# IMU.net
KiCad netlist of a schematic drawn in Altium Designer
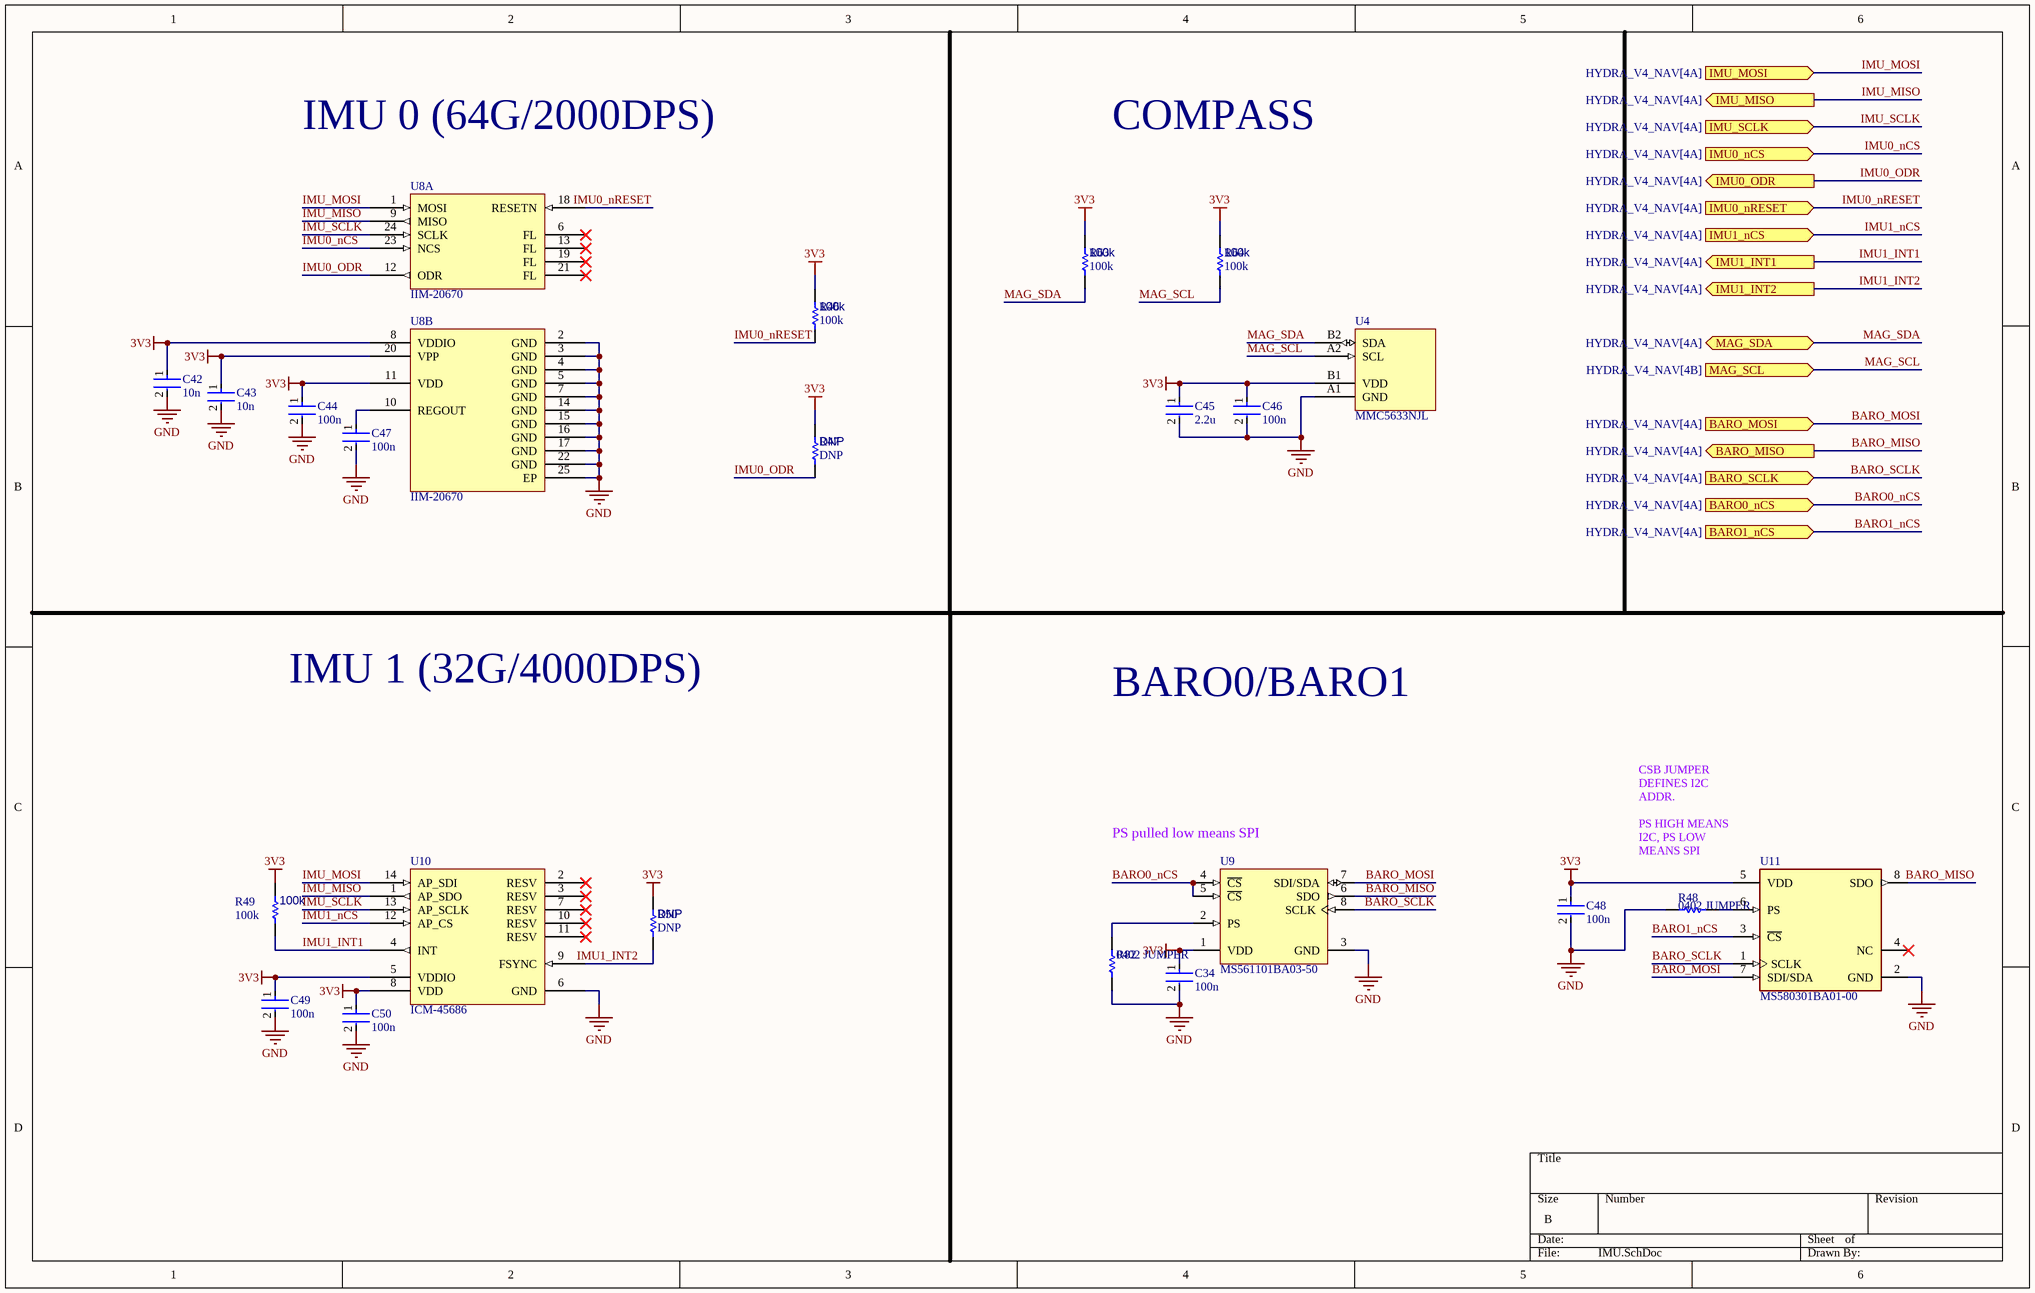
[diagram p0: IMU.SchDoc]

(export (version "E")
  (design (tool "Eeschema 10.0.6"))
  (components
    (comp (ref "C34")
      (value "100n")
      (footprint "FP-0402-L_1_0_0_05-W_0_5-IPC_A")
      (description "LARGE PADS, 0402 CAP, CHANGE COMMENT TO MATCH REAL P/N")
      (libsource (lib "Space Concordia") (part "b4654b650e69147ec39a6b967a45e02"))
    )
    (comp (ref "C42")
      (value "10n")
      (footprint "FP-0402-L_1_0_0_05-W_0_5-IPC_A")
      (description "LARGE PADS, 0402 CAP, CHANGE COMMENT TO MATCH REAL P/N")
      (libsource (lib "Space Concordia") (part "b4654b650e69147ec39a6b967a45e02"))
    )
    (comp (ref "C43")
      (value "10n")
      (footprint "FP-0402-L_1_0_0_05-W_0_5-IPC_A")
      (description "LARGE PADS, 0402 CAP, CHANGE COMMENT TO MATCH REAL P/N")
      (libsource (lib "Space Concordia") (part "b4654b650e69147ec39a6b967a45e02"))
    )
    (comp (ref "C44")
      (value "100n")
      (footprint "FP-0402-L_1_0_0_05-W_0_5-IPC_A")
      (description "LARGE PADS, 0402 CAP, CHANGE COMMENT TO MATCH REAL P/N")
      (libsource (lib "Space Concordia") (part "b4654b650e69147ec39a6b967a45e02"))
    )
    (comp (ref "C45")
      (value "2.2u")
      (footprint "FP-0402-L_1_0_0_05-W_0_5-IPC_A")
      (description "LARGE PADS, 0402 CAP, CHANGE COMMENT TO MATCH REAL P/N")
      (libsource (lib "Space Concordia") (part "b4654b650e69147ec39a6b967a45e02"))
    )
    (comp (ref "C46")
      (value "100n")
      (footprint "FP-0402-L_1_0_0_05-W_0_5-IPC_A")
      (description "LARGE PADS, 0402 CAP, CHANGE COMMENT TO MATCH REAL P/N")
      (libsource (lib "Space Concordia") (part "b4654b650e69147ec39a6b967a45e02"))
    )
    (comp (ref "C47")
      (value "100n")
      (footprint "FP-0402-L_1_0_0_05-W_0_5-IPC_A")
      (description "LARGE PADS, 0402 CAP, CHANGE COMMENT TO MATCH REAL P/N")
      (libsource (lib "Space Concordia") (part "b4654b650e69147ec39a6b967a45e02"))
    )
    (comp (ref "C48")
      (value "100n")
      (footprint "FP-0402-L_1_0_0_05-W_0_5-IPC_A")
      (description "LARGE PADS, 0402 CAP, CHANGE COMMENT TO MATCH REAL P/N")
      (libsource (lib "Space Concordia") (part "b4654b650e69147ec39a6b967a45e02"))
    )
    (comp (ref "C49")
      (value "100n")
      (footprint "FP-0402-L_1_0_0_05-W_0_5-IPC_A")
      (description "LARGE PADS, 0402 CAP, CHANGE COMMENT TO MATCH REAL P/N")
      (libsource (lib "Space Concordia") (part "b4654b650e69147ec39a6b967a45e02"))
    )
    (comp (ref "C50")
      (value "100n")
      (footprint "FP-0402-L_1_0_0_05-W_0_5-IPC_A")
      (description "LARGE PADS, 0402 CAP, CHANGE COMMENT TO MATCH REAL P/N")
      (libsource (lib "Space Concordia") (part "b4654b650e69147ec39a6b967a45e02"))
    )
    (comp (ref "R46")
      (value "100k")
      (footprint "R0603B")
      (description "Resistor")
      (fields (field (name "ALTIUM_VALUE") "100k"))
      (libsource (lib "Space Concordia") (part "Resistor"))
    )
    (comp (ref "R47")
      (value "DNP")
      (footprint "R0603B")
      (description "Resistor")
      (fields (field (name "ALTIUM_VALUE") "DNP"))
      (libsource (lib "Space Concordia") (part "Resistor"))
    )
    (comp (ref "R48")
      (value "0402 JUMPER")
      (footprint "RESC1005X40X25ML05T05")
      (description "READ THE NAME")
      (libsource (lib "Space Concordia") (part "CMP-009-00206-2"))
    )
    (comp (ref "R49")
      (value "100k")
      (footprint "R0603B")
      (description "Resistor")
      (fields (field (name "ALTIUM_VALUE") "100k"))
      (libsource (lib "Space Concordia") (part "Resistor"))
    )
    (comp (ref "R50")
      (value "DNP")
      (footprint "R0603B")
      (description "Resistor")
      (fields (field (name "ALTIUM_VALUE") "DNP"))
      (libsource (lib "Space Concordia") (part "Resistor"))
    )
    (comp (ref "R63")
      (value "100k")
      (footprint "R0603B")
      (description "Resistor")
      (fields (field (name "ALTIUM_VALUE") "100k"))
      (libsource (lib "Space Concordia") (part "Resistor"))
    )
    (comp (ref "R64")
      (value "100k")
      (footprint "R0603B")
      (description "Resistor")
      (fields (field (name "ALTIUM_VALUE") "100k"))
      (libsource (lib "Space Concordia") (part "Resistor"))
    )
    (comp (ref "R82")
      (value "0402 JUMPER")
      (footprint "RESC1005X40X25ML05T05")
      (description "READ THE NAME")
      (libsource (lib "Space Concordia") (part "CMP-009-00206-2"))
    )
    (comp (ref "U4")
      (value "MMC5633NJL")
      (footprint "BGA4C40P2X2_85X85X60")
      (description "Magnetoresistive Sensor X, Y, Z Axis 4-WLP (0.85x0.85)")
      (libsource (lib "Space Concordia") (part "MMC5633NJL-Symbol-1"))
    )
    (comp (ref "U8")
      (value "IIM-20670")
      (footprint "PQFN50P450X450X115_HS-25N")
      (description "6-axis IMU with extended temperature range and high VRE performance")
      (libsource (lib "Space Concordia") (part "IIM-20670"))
    )
    (comp (ref "U9")
      (value "MS561101BA03-50")
      (footprint "MSI-MS561101BA03-50-8_V")
      (fields (field (name "MANUFACTURER") "Measurement Specialties"))
      (libsource (lib "Altium Content Vault") (part "MSI-MS561101BA03-50-8"))
    )
    (comp (ref "U10")
      (value "ICM-45686")
      (footprint "PQFN50P300X250X86-14N")
      (description "Ultra High-Performance 6-Axis MEMS Motion Sensor")
      (libsource (lib "Space Concordia") (part "ICM-45686"))
    )
    (comp (ref "U11")
      (value "MS580301BA01-00")
      (footprint "FP-MS580301BA01-00-MFG")
      (description "MINIATURE ALTIMETER MODULE")
      (fields
        (field (name "MANUFACTURER") "TE Connectivity")
        (field (name "OCTOPART") "https://octopart.com/ms580301ba01-00-te+connectivity-59208927")
      )
      (libsource (lib "Altium Content Vault") (part "12a5185c47872775e691a69d0eb4388"))
    )
  )
  (nets
    (net (code "1") (name "/BARO0_nCS") (class "Default")
      (node (ref "U9") (pin "4") (pinfunction "~{CS}_4") (pintype "input"))
      (node (ref "U9") (pin "5") (pinfunction "~{CS}_5") (pintype "input"))
    )
    (net (code "2") (name "/BARO1_nCS") (class "Default")
      (node (ref "U11") (pin "3") (pinfunction "~{CS}_3") (pintype "input"))
    )
    (net (code "3") (name "/BARO_MISO") (class "Default")
      (node (ref "U11") (pin "8") (pinfunction "SDO_8") (pintype "output"))
      (node (ref "U9") (pin "6") (pinfunction "SDO_6") (pintype "output"))
    )
    (net (code "4") (name "/BARO_MOSI") (class "Default")
      (node (ref "U11") (pin "7") (pinfunction "SDI/SDA_7") (pintype "input"))
      (node (ref "U9") (pin "7") (pinfunction "SDI/SDA_7") (pintype "bidirectional"))
    )
    (net (code "5") (name "/BARO_SCLK") (class "Default")
      (node (ref "U11") (pin "1") (pinfunction "SCLK_1") (pintype "input"))
      (node (ref "U9") (pin "8") (pinfunction "SCLK_8") (pintype "input"))
    )
    (net (code "6") (name "/IMU0_ODR") (class "Default")
      (node (ref "R47") (pin "2") (pinfunction "2_2") (pintype "passive"))
      (node (ref "U8") (pin "12") (pinfunction "ODR_12") (pintype "output"))
    )
    (net (code "7") (name "/IMU0_nCS") (class "Default")
      (node (ref "U8") (pin "23") (pinfunction "NCS_23") (pintype "input"))
    )
    (net (code "8") (name "/IMU0_nRESET") (class "Default")
      (node (ref "R46") (pin "2") (pinfunction "2_2") (pintype "passive"))
      (node (ref "U8") (pin "18") (pinfunction "RESETN_18") (pintype "input"))
    )
    (net (code "9") (name "/IMU1_INT1") (class "Default")
      (node (ref "R49") (pin "2") (pinfunction "2_2") (pintype "passive"))
      (node (ref "U10") (pin "4") (pinfunction "INT_4") (pintype "output"))
    )
    (net (code "10") (name "/IMU1_INT2") (class "Default")
      (node (ref "R50") (pin "2") (pinfunction "2_2") (pintype "passive"))
      (node (ref "U10") (pin "9") (pinfunction "FSYNC_9") (pintype "input"))
    )
    (net (code "11") (name "/IMU1_nCS") (class "Default")
      (node (ref "U10") (pin "12") (pinfunction "AP_CS_12") (pintype "input"))
    )
    (net (code "12") (name "/IMU_MISO") (class "Default")
      (node (ref "U10") (pin "1") (pinfunction "AP_SDO_1") (pintype "output"))
      (node (ref "U8") (pin "9") (pinfunction "MISO_9") (pintype "output"))
    )
    (net (code "13") (name "/IMU_MOSI") (class "Default")
      (node (ref "U10") (pin "14") (pinfunction "AP_SDI_14") (pintype "input"))
      (node (ref "U8") (pin "1") (pinfunction "MOSI_1") (pintype "input"))
    )
    (net (code "14") (name "/IMU_SCLK") (class "Default")
      (node (ref "U10") (pin "13") (pinfunction "AP_SCLK_13") (pintype "input"))
      (node (ref "U8") (pin "24") (pinfunction "SCLK_24") (pintype "input"))
    )
    (net (code "15") (name "/MAG_SCL") (class "Default")
      (node (ref "R64") (pin "2") (pinfunction "2_2") (pintype "passive"))
      (node (ref "U4") (pin "A2") (pinfunction "SCL_A2") (pintype "input"))
    )
    (net (code "16") (name "/MAG_SDA") (class "Default")
      (node (ref "R63") (pin "2") (pinfunction "2_2") (pintype "passive"))
      (node (ref "U4") (pin "B2") (pinfunction "SDA_B2") (pintype "bidirectional"))
    )
    (net (code "17") (name "3V3") (class "Default")
      (node (ref "C34") (pin "1") (pinfunction "1_1") (pintype "passive"))
      (node (ref "C42") (pin "1") (pinfunction "1_1") (pintype "passive"))
      (node (ref "C43") (pin "1") (pinfunction "1_1") (pintype "passive"))
      (node (ref "C44") (pin "1") (pinfunction "1_1") (pintype "passive"))
      (node (ref "C45") (pin "1") (pinfunction "1_1") (pintype "passive"))
      (node (ref "C46") (pin "1") (pinfunction "1_1") (pintype "passive"))
      (node (ref "C48") (pin "1") (pinfunction "1_1") (pintype "passive"))
      (node (ref "C49") (pin "1") (pinfunction "1_1") (pintype "passive"))
      (node (ref "C50") (pin "1") (pinfunction "1_1") (pintype "passive"))
      (node (ref "R46") (pin "1") (pinfunction "1_1") (pintype "passive"))
      (node (ref "R47") (pin "1") (pinfunction "1_1") (pintype "passive"))
      (node (ref "R49") (pin "1") (pinfunction "1_1") (pintype "passive"))
      (node (ref "R50") (pin "1") (pinfunction "1_1") (pintype "passive"))
      (node (ref "R63") (pin "1") (pinfunction "1_1") (pintype "passive"))
      (node (ref "R64") (pin "1") (pinfunction "1_1") (pintype "passive"))
      (node (ref "U10") (pin "5") (pinfunction "VDDIO_5") (pintype "power_in"))
      (node (ref "U10") (pin "8") (pinfunction "VDD_8") (pintype "power_in"))
      (node (ref "U11") (pin "5") (pinfunction "VDD_5") (pintype "power_in"))
      (node (ref "U4") (pin "B1") (pinfunction "VDD_B1") (pintype "power_in"))
      (node (ref "U8") (pin "11") (pinfunction "VDD_11") (pintype "power_in"))
      (node (ref "U8") (pin "20") (pinfunction "VPP_20") (pintype "power_in"))
      (node (ref "U8") (pin "8") (pinfunction "VDDIO_8") (pintype "power_in"))
      (node (ref "U9") (pin "1") (pinfunction "VDD_1") (pintype "power_in"))
    )
    (net (code "18") (name "GND") (class "Default")
      (node (ref "C34") (pin "2") (pinfunction "2_2") (pintype "passive"))
      (node (ref "C42") (pin "2") (pinfunction "2_2") (pintype "passive"))
      (node (ref "C43") (pin "2") (pinfunction "2_2") (pintype "passive"))
      (node (ref "C44") (pin "2") (pinfunction "2_2") (pintype "passive"))
      (node (ref "C45") (pin "2") (pinfunction "2_2") (pintype "passive"))
      (node (ref "C46") (pin "2") (pinfunction "2_2") (pintype "passive"))
      (node (ref "C47") (pin "2") (pinfunction "2_2") (pintype "passive"))
      (node (ref "C48") (pin "2") (pinfunction "2_2") (pintype "passive"))
      (node (ref "C49") (pin "2") (pinfunction "2_2") (pintype "passive"))
      (node (ref "C50") (pin "2") (pinfunction "2_2") (pintype "passive"))
      (node (ref "R48") (pin "2") (pinfunction "2_2") (pintype "passive"))
      (node (ref "R82") (pin "1") (pinfunction "1_1") (pintype "passive"))
      (node (ref "U10") (pin "6") (pinfunction "GND_6") (pintype "power_in"))
      (node (ref "U11") (pin "2") (pinfunction "GND_2") (pintype "power_in"))
      (node (ref "U4") (pin "A1") (pinfunction "GND_A1") (pintype "power_in"))
      (node (ref "U8") (pin "14") (pinfunction "GND_14") (pintype "power_in"))
      (node (ref "U8") (pin "15") (pinfunction "GND_15") (pintype "power_in"))
      (node (ref "U8") (pin "16") (pinfunction "GND_16") (pintype "power_in"))
      (node (ref "U8") (pin "17") (pinfunction "GND_17") (pintype "power_in"))
      (node (ref "U8") (pin "2") (pinfunction "GND_2") (pintype "power_in"))
      (node (ref "U8") (pin "22") (pinfunction "GND_22") (pintype "power_in"))
      (node (ref "U8") (pin "25") (pinfunction "EP_25") (pintype "power_in"))
      (node (ref "U8") (pin "3") (pinfunction "GND_3") (pintype "power_in"))
      (node (ref "U8") (pin "4") (pinfunction "GND_4") (pintype "power_in"))
      (node (ref "U8") (pin "5") (pinfunction "GND_5") (pintype "power_in"))
      (node (ref "U8") (pin "7") (pinfunction "GND_7") (pintype "power_in"))
      (node (ref "U9") (pin "3") (pinfunction "GND_3") (pintype "power_in"))
    )
    (net (code "19") (name "Net-(U8B-REGOUT)") (class "Default")
      (node (ref "C47") (pin "1") (pinfunction "1_1") (pintype "passive"))
      (node (ref "U8") (pin "10") (pinfunction "REGOUT_10") (pintype "passive"))
    )
    (net (code "20") (name "Net-(U9-PS)") (class "Default")
      (node (ref "R82") (pin "2") (pinfunction "2_2") (pintype "passive"))
      (node (ref "U9") (pin "2") (pinfunction "PS_2") (pintype "input"))
    )
    (net (code "21") (name "Net-(U11-PS)") (class "Default")
      (node (ref "R48") (pin "1") (pinfunction "1_1") (pintype "passive"))
      (node (ref "U11") (pin "6") (pinfunction "PS_6") (pintype "input"))
    )
    (net (code "22") (name "unconnected-(U8A-FL-Pad6)") (class "Default")
      (node (ref "U8") (pin "6") (pinfunction "FL_6") (pintype "passive+no_connect"))
    )
    (net (code "23") (name "unconnected-(U8A-FL-Pad13)") (class "Default")
      (node (ref "U8") (pin "13") (pinfunction "FL_13") (pintype "passive+no_connect"))
    )
    (net (code "24") (name "unconnected-(U8A-FL-Pad19)") (class "Default")
      (node (ref "U8") (pin "19") (pinfunction "FL_19") (pintype "passive+no_connect"))
    )
    (net (code "25") (name "unconnected-(U8A-FL-Pad21)") (class "Default")
      (node (ref "U8") (pin "21") (pinfunction "FL_21") (pintype "passive+no_connect"))
    )
    (net (code "26") (name "unconnected-(U10-RESV-Pad2)") (class "Default")
      (node (ref "U10") (pin "2") (pinfunction "RESV_2") (pintype "passive+no_connect"))
    )
    (net (code "27") (name "unconnected-(U10-RESV-Pad3)") (class "Default")
      (node (ref "U10") (pin "3") (pinfunction "RESV_3") (pintype "passive+no_connect"))
    )
    (net (code "28") (name "unconnected-(U10-RESV-Pad7)") (class "Default")
      (node (ref "U10") (pin "7") (pinfunction "RESV_7") (pintype "passive+no_connect"))
    )
    (net (code "29") (name "unconnected-(U10-RESV-Pad10)") (class "Default")
      (node (ref "U10") (pin "10") (pinfunction "RESV_10") (pintype "passive+no_connect"))
    )
    (net (code "30") (name "unconnected-(U10-RESV-Pad11)") (class "Default")
      (node (ref "U10") (pin "11") (pinfunction "RESV_11") (pintype "passive+no_connect"))
    )
    (net (code "31") (name "unconnected-(U11-NC-Pad4)") (class "Default")
      (node (ref "U11") (pin "4") (pinfunction "NC_4") (pintype "passive+no_connect"))
    )
  )
)
